# M182B.net
KiCad netlist of a schematic drawn in EAGLE
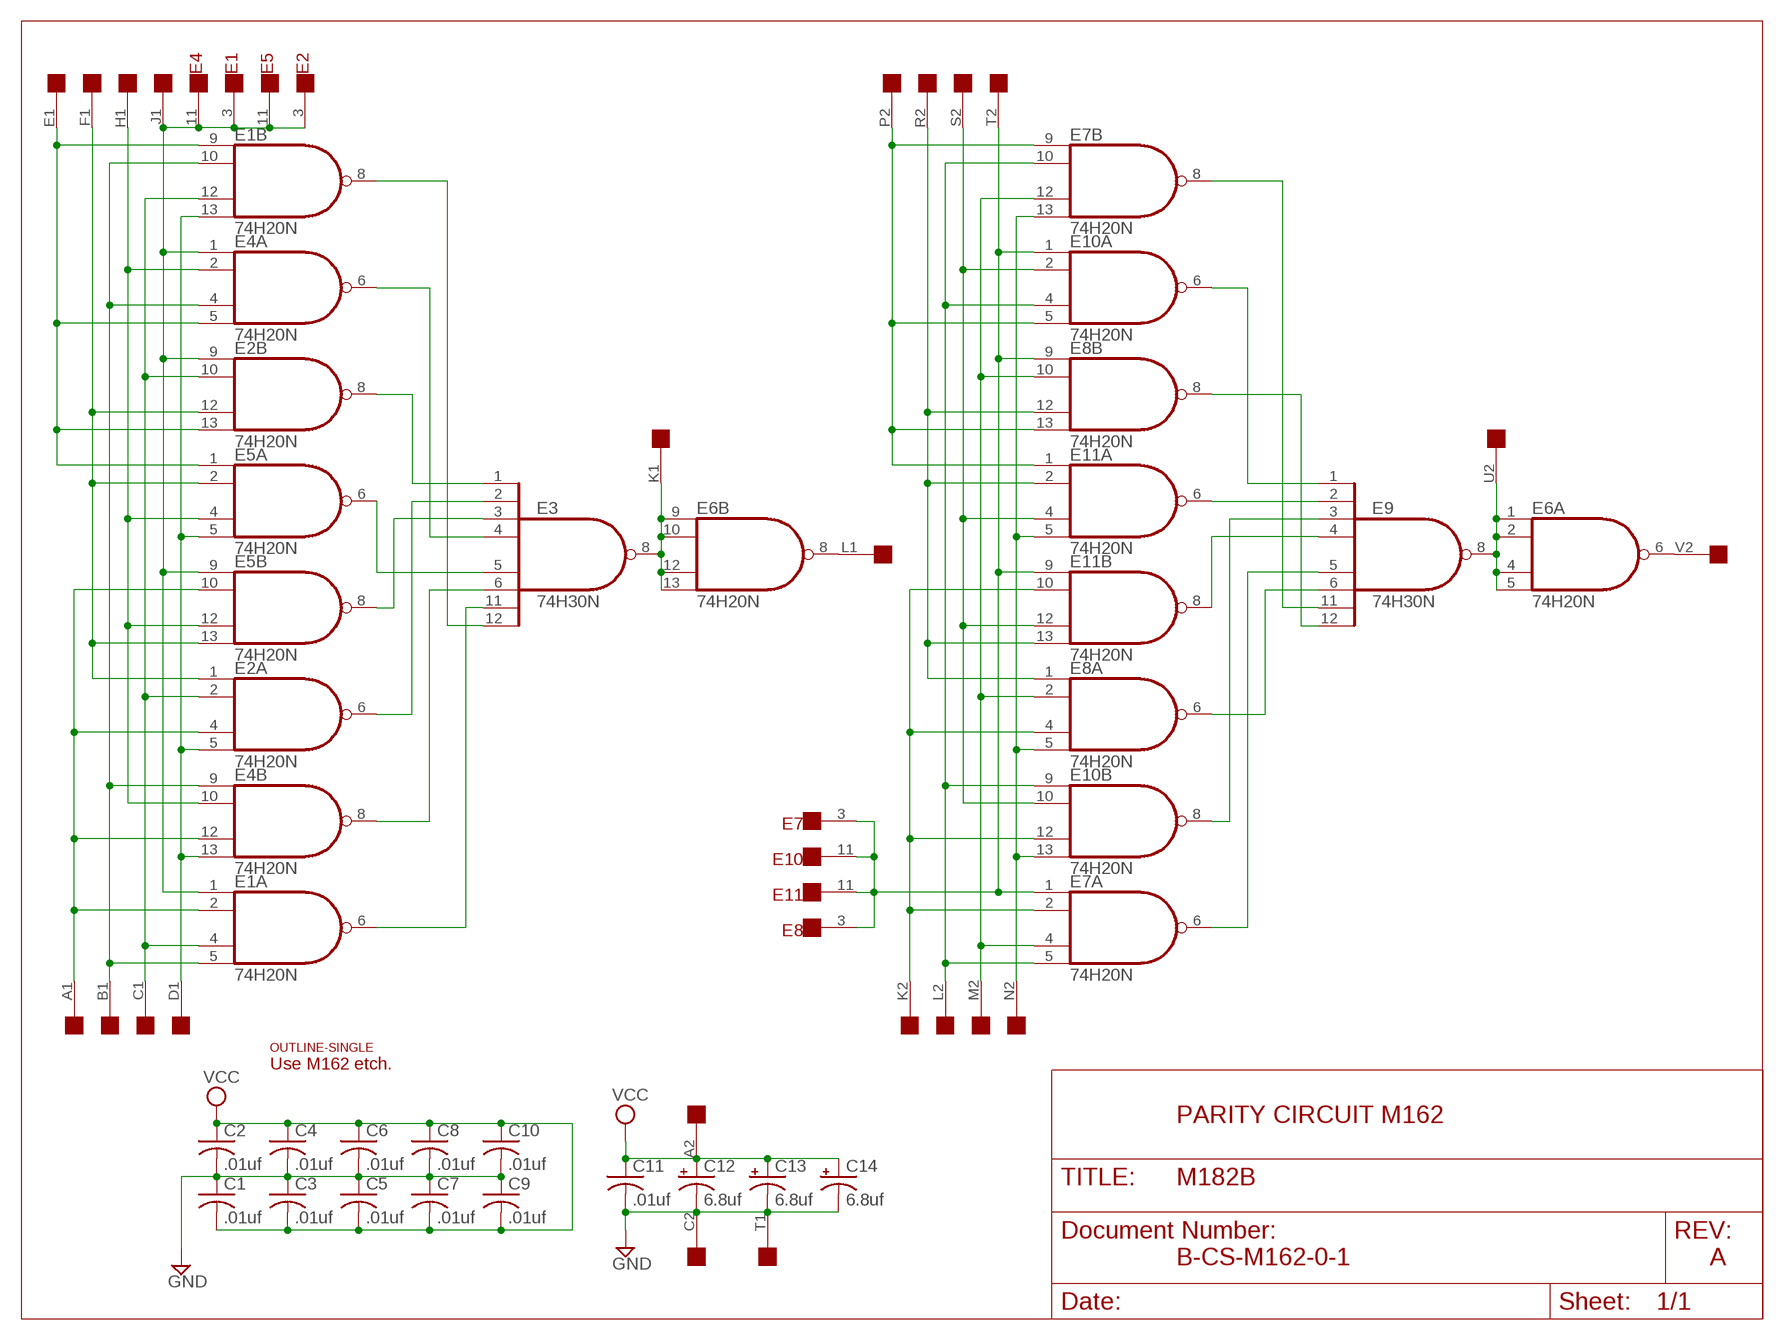
[diagram p0: schematic, sheet 1]

(export (version "E")
  (design (tool "Eeschema 10.0.6"))
  (components
    (comp (ref "C1")
      (value ".01uf")
      (footprint "eagle-import:C050-025X075")
      (libsource (lib "eagle-import") (part "C-US050-025X075"))
    )
    (comp (ref "C2")
      (value ".01uf")
      (footprint "eagle-import:C050-025X075")
      (libsource (lib "eagle-import") (part "C-US050-025X075"))
    )
    (comp (ref "C3")
      (value ".01uf")
      (footprint "eagle-import:C050-025X075")
      (libsource (lib "eagle-import") (part "C-US050-025X075"))
    )
    (comp (ref "C4")
      (value ".01uf")
      (footprint "eagle-import:C050-025X075")
      (libsource (lib "eagle-import") (part "C-US050-025X075"))
    )
    (comp (ref "C5")
      (value ".01uf")
      (footprint "eagle-import:C050-025X075")
      (libsource (lib "eagle-import") (part "C-US050-025X075"))
    )
    (comp (ref "C6")
      (value ".01uf")
      (footprint "eagle-import:C050-025X075")
      (libsource (lib "eagle-import") (part "C-US050-025X075"))
    )
    (comp (ref "C7")
      (value ".01uf")
      (footprint "eagle-import:C050-025X075")
      (libsource (lib "eagle-import") (part "C-US050-025X075"))
    )
    (comp (ref "C8")
      (value ".01uf")
      (footprint "eagle-import:C050-025X075")
      (libsource (lib "eagle-import") (part "C-US050-025X075"))
    )
    (comp (ref "C9")
      (value ".01uf")
      (footprint "eagle-import:C050-025X075")
      (libsource (lib "eagle-import") (part "C-US050-025X075"))
    )
    (comp (ref "C10")
      (value ".01uf")
      (footprint "eagle-import:C050-025X075")
      (libsource (lib "eagle-import") (part "C-US050-025X075"))
    )
    (comp (ref "C11")
      (value ".01uf")
      (footprint "eagle-import:C050-025X075")
      (libsource (lib "eagle-import") (part "C-US050-025X075"))
    )
    (comp (ref "C12")
      (value "6.8uf")
      (footprint "eagle-import:E15-5")
      (libsource (lib "eagle-import") (part "CPOL-USE15-5AXIAL"))
    )
    (comp (ref "C13")
      (value "6.8uf")
      (footprint "eagle-import:E15-5")
      (libsource (lib "eagle-import") (part "CPOL-USE15-5AXIAL"))
    )
    (comp (ref "C14")
      (value "6.8uf")
      (footprint "eagle-import:E15-5")
      (libsource (lib "eagle-import") (part "CPOL-USE15-5AXIAL"))
    )
    (comp (ref "E1")
      (value "74H20N")
      (footprint "eagle-import:DIL14")
      (libsource (lib "eagle-import") (part "7420NS"))
    )
    (comp (ref "E2")
      (value "74H20N")
      (footprint "eagle-import:DIL14")
      (libsource (lib "eagle-import") (part "7420NS"))
    )
    (comp (ref "E3")
      (value "74H30N")
      (footprint "eagle-import:DIL14")
      (libsource (lib "eagle-import") (part "7430N"))
    )
    (comp (ref "E4")
      (value "74H20N")
      (footprint "eagle-import:DIL14")
      (libsource (lib "eagle-import") (part "7420NS"))
    )
    (comp (ref "E5")
      (value "74H20N")
      (footprint "eagle-import:DIL14")
      (libsource (lib "eagle-import") (part "7420NS"))
    )
    (comp (ref "E6")
      (value "74H20N")
      (footprint "eagle-import:DIL14")
      (libsource (lib "eagle-import") (part "7420NS"))
    )
    (comp (ref "E7")
      (value "74H20N")
      (footprint "eagle-import:DIL14")
      (libsource (lib "eagle-import") (part "7420NS"))
    )
    (comp (ref "E8")
      (value "74H20N")
      (footprint "eagle-import:DIL14")
      (libsource (lib "eagle-import") (part "7420NS"))
    )
    (comp (ref "E9")
      (value "74H30N")
      (footprint "eagle-import:DIL14")
      (libsource (lib "eagle-import") (part "7430N"))
    )
    (comp (ref "E10")
      (value "74H20N")
      (footprint "eagle-import:DIL14")
      (libsource (lib "eagle-import") (part "7420NS"))
    )
    (comp (ref "E11")
      (value "74H20N")
      (footprint "eagle-import:DIL14")
      (libsource (lib "eagle-import") (part "7420NS"))
    )
    (comp (ref "U$1")
      (value "OUTLINE-SINGLE")
      (footprint "eagle-import:SINGLE")
      (libsource (lib "eagle-import") (part "OUTLINE-SINGLE"))
    )
    (comp (ref "U$2")
      (value "EDGE-2CONNECTOR")
      (footprint "eagle-import:EDGE-CON2")
      (libsource (lib "eagle-import") (part "EDGE-2CONNECTOR"))
    )
  )
  (nets
    (net (code "1") (name "GND") (class "Default")
      (node (ref "C1") (pin "1") (pinfunction "1_1") (pintype "passive"))
      (node (ref "C10") (pin "2") (pinfunction "2_2") (pintype "passive"))
      (node (ref "C11") (pin "2") (pinfunction "2_2") (pintype "passive"))
      (node (ref "C12") (pin "-") (pinfunction "-_-") (pintype "passive"))
      (node (ref "C13") (pin "-") (pinfunction "-_-") (pintype "passive"))
      (node (ref "C14") (pin "-") (pinfunction "-_-") (pintype "passive"))
      (node (ref "C2") (pin "2") (pinfunction "2_2") (pintype "passive"))
      (node (ref "C3") (pin "1") (pinfunction "1_1") (pintype "passive"))
      (node (ref "C4") (pin "2") (pinfunction "2_2") (pintype "passive"))
      (node (ref "C5") (pin "1") (pinfunction "1_1") (pintype "passive"))
      (node (ref "C6") (pin "2") (pinfunction "2_2") (pintype "passive"))
      (node (ref "C7") (pin "1") (pinfunction "1_1") (pintype "passive"))
      (node (ref "C8") (pin "2") (pinfunction "2_2") (pintype "passive"))
      (node (ref "C9") (pin "1") (pinfunction "1_1") (pintype "passive"))
      (node (ref "U$2") (pin "C2") (pinfunction "1_C2") (pintype "bidirectional"))
      (node (ref "U$2") (pin "T1") (pinfunction "1_T1") (pintype "bidirectional"))
    )
    (net (code "2") (name "Net-(E1B-NC)") (class "Default")
      (node (ref "E1") (pin "1") (pinfunction "I0_1") (pintype "input"))
      (node (ref "E1") (pin "3") (pinfunction "NC_3") (pintype "passive"))
      (node (ref "E2") (pin "3") (pinfunction "NC_3") (pintype "passive"))
      (node (ref "E2") (pin "9") (pinfunction "I0_9") (pintype "input"))
      (node (ref "E4") (pin "1") (pinfunction "I0_1") (pintype "input"))
      (node (ref "E4") (pin "11") (pinfunction "NC_11") (pintype "passive"))
      (node (ref "E5") (pin "11") (pinfunction "NC_11") (pintype "passive"))
      (node (ref "E5") (pin "9") (pinfunction "I0_9") (pintype "input"))
      (node (ref "U$2") (pin "J1") (pinfunction "1_J1") (pintype "bidirectional"))
    )
    (net (code "3") (name "Net-(E1C-I1)") (class "Default")
      (node (ref "E1") (pin "2") (pinfunction "I1_2") (pintype "input"))
      (node (ref "E2") (pin "4") (pinfunction "I2_4") (pintype "input"))
      (node (ref "E4") (pin "12") (pinfunction "I2_12") (pintype "input"))
      (node (ref "E5") (pin "10") (pinfunction "I1_10") (pintype "input"))
      (node (ref "U$2") (pin "A1") (pinfunction "1_A1") (pintype "bidirectional"))
    )
    (net (code "4") (name "Net-(E1C-I2)") (class "Default")
      (node (ref "E1") (pin "12") (pinfunction "I2_12") (pintype "input"))
      (node (ref "E1") (pin "4") (pinfunction "I2_4") (pintype "input"))
      (node (ref "E2") (pin "10") (pinfunction "I1_10") (pintype "input"))
      (node (ref "E2") (pin "2") (pinfunction "I1_2") (pintype "input"))
      (node (ref "U$2") (pin "C1") (pinfunction "1_C1") (pintype "bidirectional"))
    )
    (net (code "5") (name "Net-(E1C-I3)") (class "Default")
      (node (ref "E1") (pin "10") (pinfunction "I1_10") (pintype "input"))
      (node (ref "E1") (pin "5") (pinfunction "I3_5") (pintype "input"))
      (node (ref "E4") (pin "4") (pinfunction "I2_4") (pintype "input"))
      (node (ref "E4") (pin "9") (pinfunction "I0_9") (pintype "input"))
      (node (ref "U$2") (pin "B1") (pinfunction "1_B1") (pintype "bidirectional"))
    )
    (net (code "6") (name "Net-(E1C-O)") (class "Default")
      (node (ref "E1") (pin "6") (pinfunction "O_6") (pintype "output"))
      (node (ref "E3") (pin "11") (pinfunction "I6_11") (pintype "input"))
    )
    (net (code "7") (name "Net-(E1D-I0)") (class "Default")
      (node (ref "E1") (pin "9") (pinfunction "I0_9") (pintype "input"))
      (node (ref "E2") (pin "13") (pinfunction "I3_13") (pintype "input"))
      (node (ref "E4") (pin "5") (pinfunction "I3_5") (pintype "input"))
      (node (ref "E5") (pin "1") (pinfunction "I0_1") (pintype "input"))
      (node (ref "U$2") (pin "E1") (pinfunction "1_E1") (pintype "bidirectional"))
    )
    (net (code "8") (name "Net-(E1D-I3)") (class "Default")
      (node (ref "E1") (pin "13") (pinfunction "I3_13") (pintype "input"))
      (node (ref "E2") (pin "5") (pinfunction "I3_5") (pintype "input"))
      (node (ref "E4") (pin "13") (pinfunction "I3_13") (pintype "input"))
      (node (ref "E5") (pin "5") (pinfunction "I3_5") (pintype "input"))
      (node (ref "U$2") (pin "D1") (pinfunction "1_D1") (pintype "bidirectional"))
    )
    (net (code "9") (name "Net-(E1D-O)") (class "Default")
      (node (ref "E1") (pin "8") (pinfunction "O_8") (pintype "output"))
      (node (ref "E3") (pin "12") (pinfunction "I7_12") (pintype "input"))
    )
    (net (code "10") (name "Net-(E2C-I0)") (class "Default")
      (node (ref "E2") (pin "1") (pinfunction "I0_1") (pintype "input"))
      (node (ref "E2") (pin "12") (pinfunction "I2_12") (pintype "input"))
      (node (ref "E5") (pin "13") (pinfunction "I3_13") (pintype "input"))
      (node (ref "E5") (pin "2") (pinfunction "I1_2") (pintype "input"))
      (node (ref "U$2") (pin "F1") (pinfunction "1_F1") (pintype "bidirectional"))
    )
    (net (code "11") (name "Net-(E2C-O)") (class "Default")
      (node (ref "E2") (pin "6") (pinfunction "O_6") (pintype "output"))
      (node (ref "E3") (pin "2") (pinfunction "I1_2") (pintype "input"))
    )
    (net (code "12") (name "Net-(E2D-O)") (class "Default")
      (node (ref "E2") (pin "8") (pinfunction "O_8") (pintype "output"))
      (node (ref "E3") (pin "1") (pinfunction "I0_1") (pintype "input"))
    )
    (net (code "13") (name "Net-(E3A-I2)") (class "Default")
      (node (ref "E3") (pin "3") (pinfunction "I2_3") (pintype "input"))
      (node (ref "E5") (pin "8") (pinfunction "O_8") (pintype "output"))
    )
    (net (code "14") (name "Net-(E3A-I3)") (class "Default")
      (node (ref "E3") (pin "4") (pinfunction "I3_4") (pintype "input"))
      (node (ref "E4") (pin "6") (pinfunction "O_6") (pintype "output"))
    )
    (net (code "15") (name "Net-(E3A-I4)") (class "Default")
      (node (ref "E3") (pin "5") (pinfunction "I4_5") (pintype "input"))
      (node (ref "E5") (pin "6") (pinfunction "O_6") (pintype "output"))
    )
    (net (code "16") (name "Net-(E3A-I5)") (class "Default")
      (node (ref "E3") (pin "6") (pinfunction "I5_6") (pintype "input"))
      (node (ref "E4") (pin "8") (pinfunction "O_8") (pintype "output"))
    )
    (net (code "17") (name "Net-(E3A-O)") (class "Default")
      (node (ref "E3") (pin "8") (pinfunction "O_8") (pintype "output"))
      (node (ref "E6") (pin "10") (pinfunction "I1_10") (pintype "input"))
      (node (ref "E6") (pin "12") (pinfunction "I2_12") (pintype "input"))
      (node (ref "E6") (pin "13") (pinfunction "I3_13") (pintype "input"))
      (node (ref "E6") (pin "9") (pinfunction "I0_9") (pintype "input"))
      (node (ref "U$2") (pin "K1") (pinfunction "1_K1") (pintype "bidirectional"))
    )
    (net (code "18") (name "Net-(E4C-I1)") (class "Default")
      (node (ref "E4") (pin "10") (pinfunction "I1_10") (pintype "input"))
      (node (ref "E4") (pin "2") (pinfunction "I1_2") (pintype "input"))
      (node (ref "E5") (pin "12") (pinfunction "I2_12") (pintype "input"))
      (node (ref "E5") (pin "4") (pinfunction "I2_4") (pintype "input"))
      (node (ref "U$2") (pin "H1") (pinfunction "1_H1") (pintype "bidirectional"))
    )
    (net (code "19") (name "Net-(E6C-I0)") (class "Default")
      (node (ref "E6") (pin "1") (pinfunction "I0_1") (pintype "input"))
      (node (ref "E6") (pin "2") (pinfunction "I1_2") (pintype "input"))
      (node (ref "E6") (pin "4") (pinfunction "I2_4") (pintype "input"))
      (node (ref "E6") (pin "5") (pinfunction "I3_5") (pintype "input"))
      (node (ref "E9") (pin "8") (pinfunction "O_8") (pintype "output"))
      (node (ref "U$2") (pin "U2") (pinfunction "1_U2") (pintype "bidirectional"))
    )
    (net (code "20") (name "Net-(E6C-O)") (class "Default")
      (node (ref "E6") (pin "6") (pinfunction "O_6") (pintype "output"))
      (node (ref "U$2") (pin "V2") (pinfunction "1_V2") (pintype "bidirectional"))
    )
    (net (code "21") (name "Net-(E6D-O)") (class "Default")
      (node (ref "E6") (pin "8") (pinfunction "O_8") (pintype "output"))
      (node (ref "U$2") (pin "L1") (pinfunction "1_L1") (pintype "bidirectional"))
    )
    (net (code "22") (name "Net-(E7C-I2)") (class "Default")
      (node (ref "E7") (pin "12") (pinfunction "I2_12") (pintype "input"))
      (node (ref "E7") (pin "4") (pinfunction "I2_4") (pintype "input"))
      (node (ref "E8") (pin "10") (pinfunction "I1_10") (pintype "input"))
      (node (ref "E8") (pin "2") (pinfunction "I1_2") (pintype "input"))
      (node (ref "U$2") (pin "M2") (pinfunction "1_M2") (pintype "bidirectional"))
    )
    (net (code "23") (name "Net-(E7C-O)") (class "Default")
      (node (ref "E7") (pin "6") (pinfunction "O_6") (pintype "output"))
      (node (ref "E9") (pin "5") (pinfunction "I4_5") (pintype "input"))
    )
    (net (code "24") (name "Net-(E7D-O)") (class "Default")
      (node (ref "E7") (pin "8") (pinfunction "O_8") (pintype "output"))
      (node (ref "E9") (pin "11") (pinfunction "I6_11") (pintype "input"))
    )
    (net (code "25") (name "Net-(E8C-O)") (class "Default")
      (node (ref "E8") (pin "6") (pinfunction "O_6") (pintype "output"))
      (node (ref "E9") (pin "6") (pinfunction "I5_6") (pintype "input"))
    )
    (net (code "26") (name "Net-(E8D-O)") (class "Default")
      (node (ref "E8") (pin "8") (pinfunction "O_8") (pintype "output"))
      (node (ref "E9") (pin "12") (pinfunction "I7_12") (pintype "input"))
    )
    (net (code "27") (name "Net-(E10A-NC)") (class "Default")
      (node (ref "E10") (pin "1") (pinfunction "I0_1") (pintype "input"))
      (node (ref "E10") (pin "11") (pinfunction "NC_11") (pintype "passive"))
      (node (ref "E11") (pin "11") (pinfunction "NC_11") (pintype "passive"))
      (node (ref "E11") (pin "9") (pinfunction "I0_9") (pintype "input"))
      (node (ref "E7") (pin "1") (pinfunction "I0_1") (pintype "input"))
      (node (ref "E7") (pin "3") (pinfunction "NC_3") (pintype "passive"))
      (node (ref "E8") (pin "3") (pinfunction "NC_3") (pintype "passive"))
      (node (ref "E8") (pin "9") (pinfunction "I0_9") (pintype "input"))
      (node (ref "U$2") (pin "T2") (pinfunction "1_T2") (pintype "bidirectional"))
    )
    (net (code "28") (name "Net-(E10C-I1)") (class "Default")
      (node (ref "E10") (pin "10") (pinfunction "I1_10") (pintype "input"))
      (node (ref "E10") (pin "2") (pinfunction "I1_2") (pintype "input"))
      (node (ref "E11") (pin "12") (pinfunction "I2_12") (pintype "input"))
      (node (ref "E11") (pin "4") (pinfunction "I2_4") (pintype "input"))
      (node (ref "U$2") (pin "S2") (pinfunction "1_S2") (pintype "bidirectional"))
    )
    (net (code "29") (name "Net-(E10C-I2)") (class "Default")
      (node (ref "E10") (pin "4") (pinfunction "I2_4") (pintype "input"))
      (node (ref "E10") (pin "9") (pinfunction "I0_9") (pintype "input"))
      (node (ref "E7") (pin "10") (pinfunction "I1_10") (pintype "input"))
      (node (ref "E7") (pin "5") (pinfunction "I3_5") (pintype "input"))
      (node (ref "U$2") (pin "L2") (pinfunction "1_L2") (pintype "bidirectional"))
    )
    (net (code "30") (name "Net-(E10C-I3)") (class "Default")
      (node (ref "E10") (pin "5") (pinfunction "I3_5") (pintype "input"))
      (node (ref "E11") (pin "1") (pinfunction "I0_1") (pintype "input"))
      (node (ref "E7") (pin "9") (pinfunction "I0_9") (pintype "input"))
      (node (ref "E8") (pin "13") (pinfunction "I3_13") (pintype "input"))
      (node (ref "U$2") (pin "P2") (pinfunction "1_P2") (pintype "bidirectional"))
    )
    (net (code "31") (name "Net-(E10C-O)") (class "Default")
      (node (ref "E10") (pin "6") (pinfunction "O_6") (pintype "output"))
      (node (ref "E9") (pin "1") (pinfunction "I0_1") (pintype "input"))
    )
    (net (code "32") (name "Net-(E10D-I2)") (class "Default")
      (node (ref "E10") (pin "12") (pinfunction "I2_12") (pintype "input"))
      (node (ref "E11") (pin "10") (pinfunction "I1_10") (pintype "input"))
      (node (ref "E7") (pin "2") (pinfunction "I1_2") (pintype "input"))
      (node (ref "E8") (pin "4") (pinfunction "I2_4") (pintype "input"))
      (node (ref "U$2") (pin "K2") (pinfunction "1_K2") (pintype "bidirectional"))
    )
    (net (code "33") (name "Net-(E10D-I3)") (class "Default")
      (node (ref "E10") (pin "13") (pinfunction "I3_13") (pintype "input"))
      (node (ref "E11") (pin "5") (pinfunction "I3_5") (pintype "input"))
      (node (ref "E7") (pin "13") (pinfunction "I3_13") (pintype "input"))
      (node (ref "E8") (pin "5") (pinfunction "I3_5") (pintype "input"))
      (node (ref "U$2") (pin "N2") (pinfunction "1_N2") (pintype "bidirectional"))
    )
    (net (code "34") (name "Net-(E10D-O)") (class "Default")
      (node (ref "E10") (pin "8") (pinfunction "O_8") (pintype "output"))
      (node (ref "E9") (pin "3") (pinfunction "I2_3") (pintype "input"))
    )
    (net (code "35") (name "Net-(E11C-I1)") (class "Default")
      (node (ref "E11") (pin "13") (pinfunction "I3_13") (pintype "input"))
      (node (ref "E11") (pin "2") (pinfunction "I1_2") (pintype "input"))
      (node (ref "E8") (pin "1") (pinfunction "I0_1") (pintype "input"))
      (node (ref "E8") (pin "12") (pinfunction "I2_12") (pintype "input"))
      (node (ref "U$2") (pin "R2") (pinfunction "1_R2") (pintype "bidirectional"))
    )
    (net (code "36") (name "Net-(E11C-O)") (class "Default")
      (node (ref "E11") (pin "6") (pinfunction "O_6") (pintype "output"))
      (node (ref "E9") (pin "2") (pinfunction "I1_2") (pintype "input"))
    )
    (net (code "37") (name "Net-(E11D-O)") (class "Default")
      (node (ref "E11") (pin "8") (pinfunction "O_8") (pintype "output"))
      (node (ref "E9") (pin "4") (pinfunction "I3_4") (pintype "input"))
    )
    (net (code "38") (name "VCC") (class "Default")
      (node (ref "C1") (pin "2") (pinfunction "2_2") (pintype "passive"))
      (node (ref "C10") (pin "1") (pinfunction "1_1") (pintype "passive"))
      (node (ref "C11") (pin "1") (pinfunction "1_1") (pintype "passive"))
      (node (ref "C12") (pin "+") (pinfunction "+_+") (pintype "passive"))
      (node (ref "C13") (pin "+") (pinfunction "+_+") (pintype "passive"))
      (node (ref "C14") (pin "+") (pinfunction "+_+") (pintype "passive"))
      (node (ref "C2") (pin "1") (pinfunction "1_1") (pintype "passive"))
      (node (ref "C3") (pin "2") (pinfunction "2_2") (pintype "passive"))
      (node (ref "C4") (pin "1") (pinfunction "1_1") (pintype "passive"))
      (node (ref "C5") (pin "2") (pinfunction "2_2") (pintype "passive"))
      (node (ref "C6") (pin "1") (pinfunction "1_1") (pintype "passive"))
      (node (ref "C7") (pin "2") (pinfunction "2_2") (pintype "passive"))
      (node (ref "C8") (pin "1") (pinfunction "1_1") (pintype "passive"))
      (node (ref "C9") (pin "2") (pinfunction "2_2") (pintype "passive"))
      (node (ref "U$2") (pin "A2") (pinfunction "1_A2") (pintype "bidirectional"))
    )
  )
)
